# 2022-4T-MNT-3.net
KiCad netlist of a schematic drawn in EasyEDA Pro
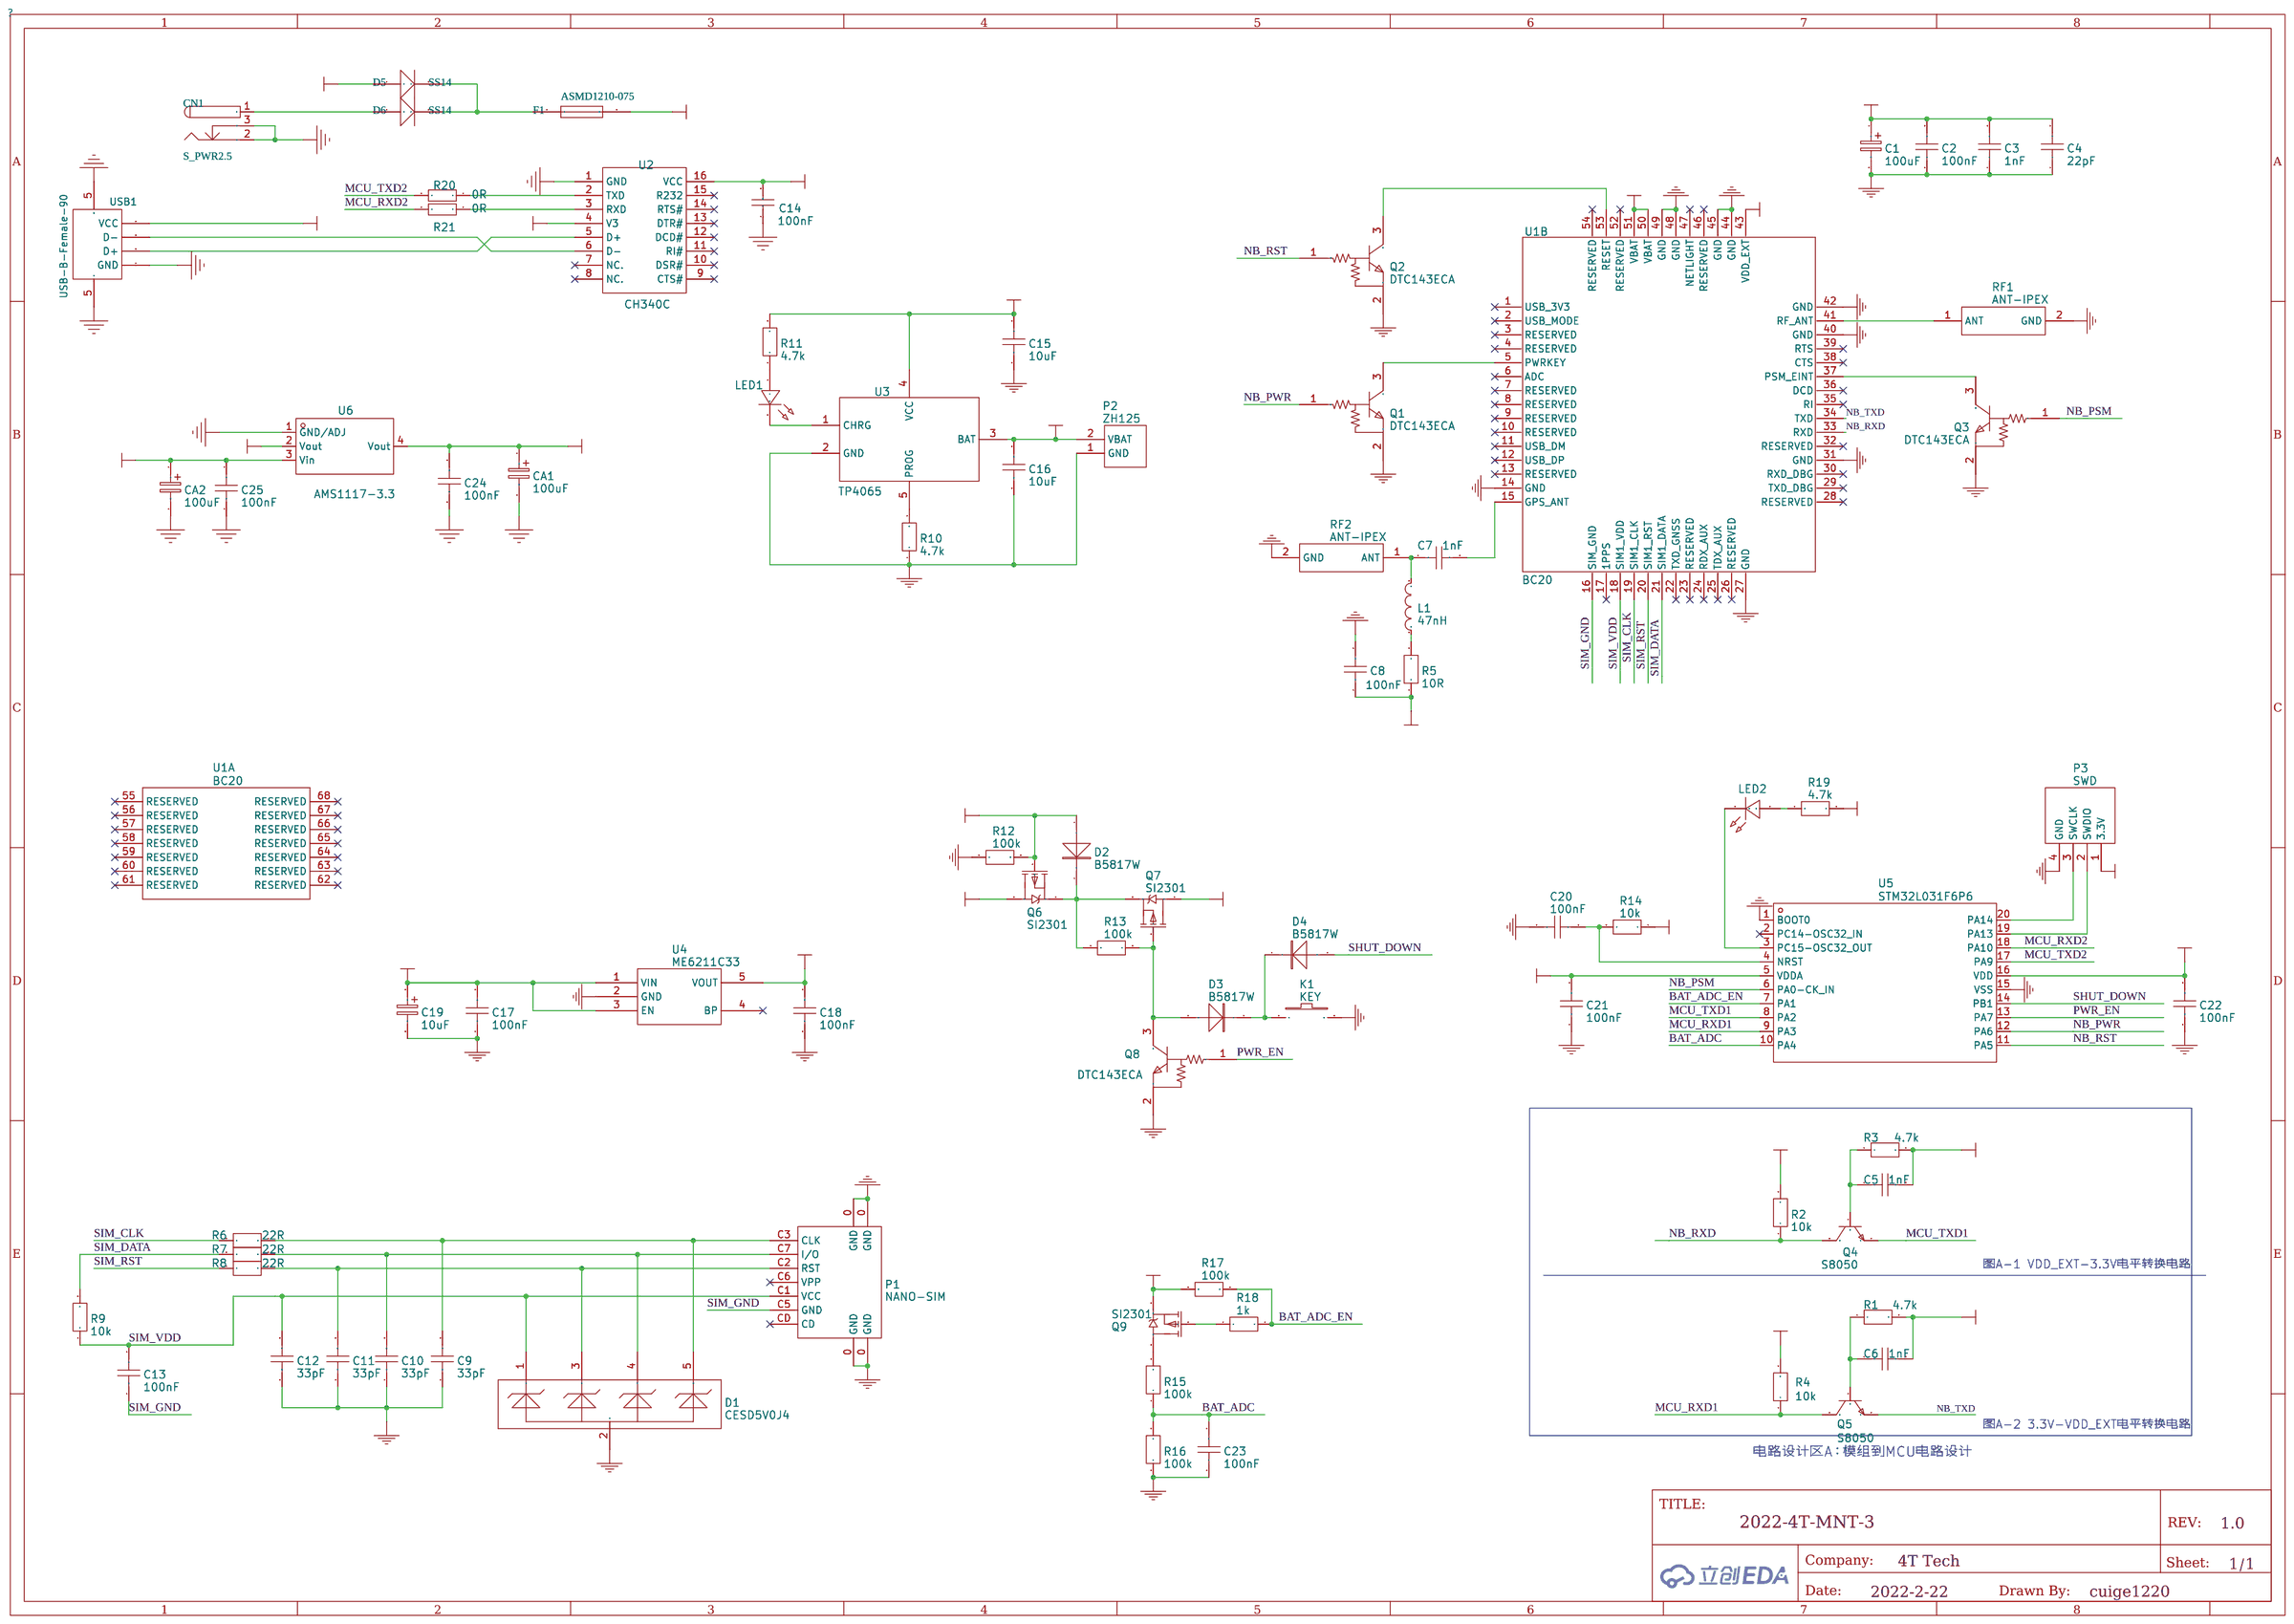
[diagram p0: schematic sheet]

(export (version "E")
  (design (tool "Eeschema 10.0.6"))
  (components
    (comp (ref "C1") (value "100uF") (libsource (lib "easyedapro") (part "100uF")))
    (comp (ref "C2")
      (value "100nF")
      (fields (field (name "Manufacturer Part") "TCC0603X7R104K500CT") (field (name "Manufacturer") "CCTC"))
      (libsource (lib "easyedapro") (part "100nF"))
    )
    (comp (ref "C3")
      (value "1nF")
      (fields (field (name "Manufacturer Part") "CL10C101JB8NNNC") (field (name "Manufacturer") "SAMSUNG"))
      (libsource (lib "easyedapro") (part "1nF"))
    )
    (comp (ref "C4") (value "22pF") (libsource (lib "easyedapro") (part "22pF")))
    (comp (ref "C5") (value "1nF") (libsource (lib "easyedapro") (part "1nF")))
    (comp (ref "C6") (value "1nF") (libsource (lib "easyedapro") (part "1nF")))
    (comp (ref "C7")
      (value "1nF")
      (fields (field (name "Manufacturer Part") "CL10C101JB8NNNC") (field (name "Manufacturer") "SAMSUNG"))
      (libsource (lib "easyedapro") (part "1nF"))
    )
    (comp (ref "C8")
      (value "100nF")
      (fields (field (name "Manufacturer Part") "TCC0603X7R104K500CT") (field (name "Manufacturer") "CCTC"))
      (libsource (lib "easyedapro") (part "100nF"))
    )
    (comp (ref "C9") (value "33pF") (libsource (lib "easyedapro") (part "33pF")))
    (comp (ref "C10") (value "33pF") (libsource (lib "easyedapro") (part "33pF")))
    (comp (ref "C11") (value "33pF") (libsource (lib "easyedapro") (part "33pF")))
    (comp (ref "C12") (value "33pF") (libsource (lib "easyedapro") (part "33pF")))
    (comp (ref "C13")
      (value "100nF")
      (fields (field (name "Manufacturer Part") "TCC0603X7R104K500CT") (field (name "Manufacturer") "CCTC"))
      (libsource (lib "easyedapro") (part "100nF"))
    )
    (comp (ref "C14")
      (value "100nF")
      (fields (field (name "Manufacturer Part") "0805F104M500NT") (field (name "Manufacturer") "FH"))
      (libsource (lib "") (part "100nF_1"))
    )
    (comp (ref "C15") (value "10uF") (libsource (lib "easyedapro") (part "10uF")))
    (comp (ref "C16") (value "10uF") (libsource (lib "easyedapro") (part "10uF")))
    (comp (ref "C17") (value "100nF") (libsource (lib "easyedapro") (part "100nF")))
    (comp (ref "C18") (value "100nF") (libsource (lib "easyedapro") (part "100nF")))
    (comp (ref "C19") (value "10uF") (libsource (lib "") (part "10uF_1")))
    (comp (ref "C20")
      (value "100nF")
      (fields (field (name "Manufacturer Part") "TCC0603X7R104K500CT") (field (name "Manufacturer") "CCTC"))
      (libsource (lib "easyedapro") (part "100nF"))
    )
    (comp (ref "C21")
      (value "100nF")
      (fields (field (name "Manufacturer Part") "TCC0603X7R104K500CT") (field (name "Manufacturer") "CCTC"))
      (libsource (lib "easyedapro") (part "100nF"))
    )
    (comp (ref "C22")
      (value "100nF")
      (fields (field (name "Manufacturer Part") "TCC0603X7R104K500CT") (field (name "Manufacturer") "CCTC"))
      (libsource (lib "easyedapro") (part "100nF"))
    )
    (comp (ref "C23")
      (value "100nF")
      (fields (field (name "Manufacturer Part") "TCC0603X7R104K500CT") (field (name "Manufacturer") "CCTC"))
      (libsource (lib "easyedapro") (part "100nF"))
    )
    (comp (ref "C24") (value "100nF") (libsource (lib "easyedapro") (part "100nF")))
    (comp (ref "C25") (value "100nF") (libsource (lib "easyedapro") (part "100nF")))
    (comp (ref "CA1") (value "100uF") (libsource (lib "easyedapro") (part "100uF")))
    (comp (ref "CA2") (value "100uF") (libsource (lib "easyedapro") (part "100uF")))
    (comp (ref "CN1") (value "S_PWR2.5") (libsource (lib "easyedapro") (part "S_PWR2.5")))
    (comp (ref "D1")
      (value "CESD5V0J4")
      (fields (field (name "Manufacturer") "CJ江苏长电"))
      (libsource (lib "easyedapro") (part "CESD5V0J4"))
    )
    (comp (ref "D2")
      (value "B5817W")
      (fields (field (name "Manufacturer") "CJ江苏长电"))
      (libsource (lib "easyedapro") (part "B5817W"))
    )
    (comp (ref "D3")
      (value "B5817W")
      (fields (field (name "Manufacturer") "CJ江苏长电"))
      (libsource (lib "easyedapro") (part "B5817W"))
    )
    (comp (ref "D4")
      (value "B5817W")
      (fields (field (name "Manufacturer") "CJ江苏长电"))
      (libsource (lib "easyedapro") (part "B5817W"))
    )
    (comp (ref "D5")
      (value "SS14")
      (fields (field (name "Publisher") "Altium Limited"))
      (libsource (lib "easyedapro") (part "SS14"))
    )
    (comp (ref "D6")
      (value "SS14")
      (fields (field (name "Publisher") "Altium Limited"))
      (libsource (lib "easyedapro") (part "SS14"))
    )
    (comp (ref "F1")
      (value "ASMD1210-075")
      (fields (field (name "Publisher") "Altium Limited"))
      (libsource (lib "easyedapro") (part "ASMD1210-075"))
    )
    (comp (ref "K1")
      (value "KEY")
      (fields (field (name "Manufacturer Part") "TSA365G00D-250") (field (name "Manufacturer") "BRIGHT(博瑞泰)"))
      (libsource (lib "easyedapro") (part "KEY"))
    )
    (comp (ref "L1") (value "47nH") (libsource (lib "easyedapro") (part "47nH")))
    (comp (ref "LED1")
      (value "LED-0805_R")
      (fields
        (field (name "Manufacturer Part") "17-21SURC/S530-A3/TR8")
        (field (name "Manufacturer") "EVERLIGHT(台湾亿光)")
      )
      (libsource (lib "easyedapro") (part "LED-0805_R"))
    )
    (comp (ref "LED2")
      (value "LED-0805_R")
      (fields
        (field (name "Manufacturer Part") "17-21SURC/S530-A3/TR8")
        (field (name "Manufacturer") "EVERLIGHT(台湾亿光)")
      )
      (libsource (lib "easyedapro") (part "LED-0805_R"))
    )
    (comp (ref "P1")
      (value "NANO-SIM")
      (fields (field (name "Manufacturer Part") "SMN-303") (field (name "Manufacturer") "XUNPU(讯普)"))
      (libsource (lib "easyedapro") (part "NANO-SIM"))
    )
    (comp (ref "P2")
      (value "ZH125")
      (fields (field (name "Manufacturer Part") "1251SMT-2P 卧贴") (field (name "Manufacturer") "Ckmtw(灿科盟)"))
      (libsource (lib "easyedapro") (part "ZH125"))
    )
    (comp (ref "P3")
      (value "SWD")
      (fields (field (name "Manufacturer Part") "A2541WV-4P") (field (name "Manufacturer") "CJT(长江连接器)"))
      (libsource (lib "easyedapro") (part "SWD"))
    )
    (comp (ref "Q1")
      (value "DTC143ECA")
      (fields (field (name "Manufacturer") "CJ江苏长电"))
      (libsource (lib "easyedapro") (part "DTC143ECA"))
    )
    (comp (ref "Q2")
      (value "DTC143ECA")
      (fields (field (name "Manufacturer") "CJ江苏长电"))
      (libsource (lib "easyedapro") (part "DTC143ECA"))
    )
    (comp (ref "Q3")
      (value "DTC143ECA")
      (fields (field (name "Manufacturer") "CJ江苏长电"))
      (libsource (lib "") (part "DTC143ECA_2"))
    )
    (comp (ref "Q4")
      (value "S8050")
      (fields (field (name "Manufacturer") "BORN伯恩半导体"))
      (libsource (lib "easyedapro") (part "S8050"))
    )
    (comp (ref "Q5")
      (value "S8050")
      (fields (field (name "Manufacturer") "BORN伯恩半导体"))
      (libsource (lib "easyedapro") (part "S8050"))
    )
    (comp (ref "Q6")
      (value "SI2301")
      (fields (field (name "Manufacturer") "Hottech(合科泰)"))
      (libsource (lib "easyedapro") (part "SI2301"))
    )
    (comp (ref "Q7")
      (value "SI2301")
      (fields (field (name "Manufacturer") "Hottech(合科泰)"))
      (libsource (lib "easyedapro") (part "SI2301"))
    )
    (comp (ref "Q8")
      (value "DTC143ECA")
      (fields (field (name "Manufacturer") "CJ江苏长电"))
      (libsource (lib "") (part "DTC143ECA_1"))
    )
    (comp (ref "Q9")
      (value "SI2301")
      (fields (field (name "Manufacturer") "Hottech(合科泰)"))
      (libsource (lib "") (part "SI2301_1"))
    )
    (comp (ref "R1") (value "4.7k") (libsource (lib "easyedapro") (part "4.7k")))
    (comp (ref "R2") (value "10k") (libsource (lib "easyedapro") (part "10k")))
    (comp (ref "R3") (value "4.7k") (libsource (lib "easyedapro") (part "4.7k")))
    (comp (ref "R4") (value "10k") (libsource (lib "easyedapro") (part "10k")))
    (comp (ref "R5") (value "10R") (libsource (lib "easyedapro") (part "10R")))
    (comp (ref "R6") (value "22R") (libsource (lib "easyedapro") (part "22R")))
    (comp (ref "R7") (value "22R") (libsource (lib "easyedapro") (part "22R")))
    (comp (ref "R8") (value "22R") (libsource (lib "easyedapro") (part "22R")))
    (comp (ref "R9") (value "10k") (libsource (lib "easyedapro") (part "10k")))
    (comp (ref "R10") (value "4.7k") (libsource (lib "easyedapro") (part "4.7k")))
    (comp (ref "R11") (value "4.7k") (libsource (lib "easyedapro") (part "4.7k")))
    (comp (ref "R12") (value "100k") (libsource (lib "easyedapro") (part "100k")))
    (comp (ref "R13") (value "100k") (libsource (lib "easyedapro") (part "100k")))
    (comp (ref "R14") (value "10k") (libsource (lib "easyedapro") (part "10k")))
    (comp (ref "R15") (value "100k") (libsource (lib "easyedapro") (part "100k")))
    (comp (ref "R16") (value "100k") (libsource (lib "easyedapro") (part "100k")))
    (comp (ref "R17") (value "100k") (libsource (lib "easyedapro") (part "100k")))
    (comp (ref "R18") (value "1k") (libsource (lib "easyedapro") (part "1k")))
    (comp (ref "R19") (value "4.7k") (libsource (lib "easyedapro") (part "4.7k")))
    (comp (ref "R20")
      (value "0R")
      (fields (field (name "Manufacturer Part") "080500J0104T5E") (field (name "Manufacturer") "UniOhm"))
      (libsource (lib "easyedapro") (part "0R"))
    )
    (comp (ref "R21")
      (value "0R")
      (fields (field (name "Manufacturer Part") "080500J0104T5E") (field (name "Manufacturer") "UniOhm"))
      (libsource (lib "easyedapro") (part "0R"))
    )
    (comp (ref "RF1")
      (value "ANT-IPEX")
      (fields
        (field (name "Manufacturer Part") "KH-IPEX-K501-29")
        (field (name "Manufacturer") "Shenzhen Kinghelm Elec")
      )
      (libsource (lib "easyedapro") (part "ANT-IPEX"))
    )
    (comp (ref "RF2")
      (value "ANT-IPEX")
      (fields
        (field (name "Manufacturer Part") "KH-IPEX-K501-29")
        (field (name "Manufacturer") "Shenzhen Kinghelm Elec")
      )
      (libsource (lib "easyedapro") (part "ANT-IPEX"))
    )
    (comp (ref "U1")
      (value "BC20")
      (fields (field (name "Manufacturer Part") "BC20NA-04-STD") (field (name "Manufacturer") "上海移远"))
      (libsource (lib "easyedapro") (part "BC20"))
    )
    (comp (ref "U2")
      (value "CH340C")
      (fields (field (name "Manufacturer") "WCH"))
      (libsource (lib "easyedapro") (part "CH340C"))
    )
    (comp (ref "U3")
      (value "TP4065")
      (fields
        (field (name "Manufacturer Part") "TP4065-4.2V-SOT25-R")
        (field (name "Manufacturer") "TOPPOWER(南京拓微)")
      )
      (libsource (lib "easyedapro") (part "TP4065"))
    )
    (comp (ref "U4")
      (value "ME6211C33")
      (fields
        (field (name "Manufacturer Part") "ME6211C33M5G-N")
        (field (name "Manufacturer") "MICRONE(南京微盟)")
      )
      (libsource (lib "easyedapro") (part "ME6211C33"))
    )
    (comp (ref "U5")
      (value "STM32L031F6P6")
      (fields (field (name "Manufacturer") "ST(意法半导体)"))
      (libsource (lib "easyedapro") (part "STM32L031F6P6"))
    )
    (comp (ref "U6")
      (value "AMS1117-3.3")
      (fields (field (name "Manufacturer") "AMS"))
      (libsource (lib "easyedapro") (part "AMS1117-3.3"))
    )
    (comp (ref "USB1")
      (value "USB-B-Female-90")
      (fields (field (name "Manufacturer Part") "USB-BF90") (field (name "Manufacturer") "ValuePro"))
      (libsource (lib "easyedapro") (part "USB-B-Female-90"))
    )
  )
  (nets
    (net (code "1") (name "+5V0") (class "Default")
      (node (ref "C25") (pin "2") (pinfunction "2_2") (pintype "input"))
      (node (ref "CA2") (pin "1") (pinfunction "1_1") (pintype "input"))
      (node (ref "F1") (pin "2") (pinfunction "2_2") (pintype "input"))
      (node (ref "U6") (pin "3") (pinfunction "Vin_3") (pintype "input"))
    )
    (net (code "2") (name "/BAT_ADC") (class "Default")
      (node (ref "C23") (pin "2") (pinfunction "2_2") (pintype "input"))
      (node (ref "R15") (pin "1") (pinfunction "1_1") (pintype "input"))
      (node (ref "R16") (pin "2") (pinfunction "2_2") (pintype "input"))
      (node (ref "U5") (pin "10") (pinfunction "PA4_10") (pintype "input"))
    )
    (net (code "3") (name "/BAT_ADC_EN") (class "Default")
      (node (ref "R17") (pin "2") (pinfunction "2_2") (pintype "input"))
      (node (ref "R18") (pin "2") (pinfunction "2_2") (pintype "input"))
      (node (ref "U5") (pin "7") (pinfunction "PA1_7") (pintype "input"))
    )
    (net (code "4") (name "/MCU_RXD1") (class "Default")
      (node (ref "Q5") (pin "3") (pinfunction "C_3") (pintype "input"))
      (node (ref "R4") (pin "1") (pinfunction "1_1") (pintype "input"))
      (node (ref "U5") (pin "9") (pinfunction "PA3_9") (pintype "input"))
    )
    (net (code "5") (name "/MCU_RXD2") (class "Default")
      (node (ref "R21") (pin "2") (pinfunction "2_2") (pintype "input"))
      (node (ref "U5") (pin "18") (pinfunction "PA10_18") (pintype "input"))
    )
    (net (code "6") (name "/MCU_TXD1") (class "Default")
      (node (ref "Q4") (pin "2") (pinfunction "E_2") (pintype "input"))
      (node (ref "U5") (pin "8") (pinfunction "PA2_8") (pintype "input"))
    )
    (net (code "7") (name "/MCU_TXD2") (class "Default")
      (node (ref "R20") (pin "2") (pinfunction "2_2") (pintype "input"))
      (node (ref "U5") (pin "17") (pinfunction "PA9_17") (pintype "input"))
    )
    (net (code "8") (name "/NB_PSM") (class "Default")
      (node (ref "Q3") (pin "1") (pinfunction "B_1") (pintype "input"))
      (node (ref "U5") (pin "6") (pinfunction "PA0-CK_IN_6") (pintype "input"))
    )
    (net (code "9") (name "/NB_PWR") (class "Default")
      (node (ref "Q1") (pin "1") (pinfunction "B_1") (pintype "input"))
      (node (ref "U5") (pin "12") (pinfunction "PA6_12") (pintype "input"))
    )
    (net (code "10") (name "/NB_RST") (class "Default")
      (node (ref "Q2") (pin "1") (pinfunction "B_1") (pintype "input"))
      (node (ref "U5") (pin "11") (pinfunction "PA5_11") (pintype "input"))
    )
    (net (code "11") (name "/NB_RXD") (class "Default")
      (node (ref "Q4") (pin "3") (pinfunction "C_3") (pintype "input"))
      (node (ref "R2") (pin "1") (pinfunction "1_1") (pintype "input"))
      (node (ref "U1") (pin "33") (pinfunction "RXD_33") (pintype "input"))
    )
    (net (code "12") (name "/NB_TXD") (class "Default")
      (node (ref "Q5") (pin "2") (pinfunction "E_2") (pintype "input"))
      (node (ref "U1") (pin "34") (pinfunction "TXD_34") (pintype "input"))
    )
    (net (code "13") (name "/PWR_EN") (class "Default")
      (node (ref "Q8") (pin "1") (pinfunction "B_1") (pintype "input"))
      (node (ref "U5") (pin "13") (pinfunction "PA7_13") (pintype "input"))
    )
    (net (code "14") (name "/SHUT_DOWN") (class "Default")
      (node (ref "D4") (pin "A") (pinfunction "A_A") (pintype "input"))
      (node (ref "U5") (pin "14") (pinfunction "PB1_14") (pintype "input"))
    )
    (net (code "15") (name "/SIM_CLK") (class "Default")
      (node (ref "R6") (pin "1") (pinfunction "1_1") (pintype "input"))
      (node (ref "U1") (pin "19") (pinfunction "SIM1_CLK_19") (pintype "input"))
    )
    (net (code "16") (name "/SIM_DATA") (class "Default")
      (node (ref "R7") (pin "1") (pinfunction "1_1") (pintype "input"))
      (node (ref "R9") (pin "2") (pinfunction "2_2") (pintype "input"))
      (node (ref "U1") (pin "21") (pinfunction "SIM1_DATA_21") (pintype "input"))
    )
    (net (code "17") (name "/SIM_GND") (class "Default")
      (node (ref "C13") (pin "1") (pinfunction "1_1") (pintype "input"))
      (node (ref "P1") (pin "C5") (pinfunction "GND_C5") (pintype "input"))
      (node (ref "U1") (pin "16") (pinfunction "SIM_GND_16") (pintype "input"))
    )
    (net (code "18") (name "/SIM_RST") (class "Default")
      (node (ref "R8") (pin "1") (pinfunction "1_1") (pintype "input"))
      (node (ref "U1") (pin "20") (pinfunction "SIM1_RST_20") (pintype "input"))
    )
    (net (code "19") (name "/SIM_VDD") (class "Default")
      (node (ref "C12") (pin "2") (pinfunction "2_2") (pintype "input"))
      (node (ref "C13") (pin "2") (pinfunction "2_2") (pintype "input"))
      (node (ref "D1") (pin "1") (pinfunction "1_1") (pintype "input"))
      (node (ref "P1") (pin "C1") (pinfunction "VCC_C1") (pintype "input"))
      (node (ref "R9") (pin "1") (pinfunction "1_1") (pintype "input"))
      (node (ref "U1") (pin "18") (pinfunction "SIM1_VDD_18") (pintype "input"))
    )
    (net (code "20") (name "3.3V") (class "Default")
      (node (ref "C1") (pin "1") (pinfunction "1_1") (pintype "input"))
      (node (ref "C14") (pin "2") (pinfunction "2_2") (pintype "input"))
      (node (ref "C18") (pin "2") (pinfunction "2_2") (pintype "input"))
      (node (ref "C2") (pin "2") (pinfunction "2_2") (pintype "input"))
      (node (ref "C21") (pin "2") (pinfunction "2_2") (pintype "input"))
      (node (ref "C22") (pin "2") (pinfunction "2_2") (pintype "input"))
      (node (ref "C24") (pin "2") (pinfunction "2_2") (pintype "input"))
      (node (ref "C3") (pin "2") (pinfunction "2_2") (pintype "input"))
      (node (ref "C4") (pin "2") (pinfunction "2_2") (pintype "input"))
      (node (ref "C5") (pin "2") (pinfunction "2_2") (pintype "input"))
      (node (ref "C8") (pin "1") (pinfunction "1_1") (pintype "input"))
      (node (ref "CA1") (pin "1") (pinfunction "1_1") (pintype "input"))
      (node (ref "P3") (pin "1") (pinfunction "3.3V_1") (pintype "input"))
      (node (ref "R14") (pin "1") (pinfunction "1_1") (pintype "input"))
      (node (ref "R19") (pin "2") (pinfunction "2_2") (pintype "input"))
      (node (ref "R3") (pin "2") (pinfunction "2_2") (pintype "input"))
      (node (ref "R4") (pin "2") (pinfunction "2_2") (pintype "input"))
      (node (ref "R5") (pin "1") (pinfunction "1_1") (pintype "input"))
      (node (ref "U1") (pin "50") (pinfunction "VBAT_50") (pintype "input"))
      (node (ref "U1") (pin "51") (pinfunction "VBAT_51") (pintype "input"))
      (node (ref "U2") (pin "16") (pinfunction "VCC_16") (pintype "input"))
      (node (ref "U2") (pin "4") (pinfunction "V3_4") (pintype "input"))
      (node (ref "U4") (pin "5") (pinfunction "VOUT_5") (pintype "input"))
      (node (ref "U5") (pin "16") (pinfunction "VDD_16") (pintype "input"))
      (node (ref "U5") (pin "5") (pinfunction "VDDA_5") (pintype "input"))
      (node (ref "U6") (pin "2") (pinfunction "Vout_2") (pintype "input"))
      (node (ref "U6") (pin "4") (pinfunction "Vout_4") (pintype "input"))
    )
    (net (code "21") (name "GND") (class "Default")
      (node (ref "C1") (pin "2") (pinfunction "2_2") (pintype "input"))
      (node (ref "C10") (pin "1") (pinfunction "1_1") (pintype "input"))
      (node (ref "C11") (pin "1") (pinfunction "1_1") (pintype "input"))
      (node (ref "C12") (pin "1") (pinfunction "1_1") (pintype "input"))
      (node (ref "C14") (pin "1") (pinfunction "1_1") (pintype "input"))
      (node (ref "C15") (pin "1") (pinfunction "1_1") (pintype "input"))
      (node (ref "C16") (pin "1") (pinfunction "1_1") (pintype "input"))
      (node (ref "C17") (pin "1") (pinfunction "1_1") (pintype "input"))
      (node (ref "C18") (pin "1") (pinfunction "1_1") (pintype "input"))
      (node (ref "C19") (pin "2") (pinfunction "2_2") (pintype "input"))
      (node (ref "C2") (pin "1") (pinfunction "1_1") (pintype "input"))
      (node (ref "C20") (pin "1") (pinfunction "1_1") (pintype "input"))
      (node (ref "C21") (pin "1") (pinfunction "1_1") (pintype "input"))
      (node (ref "C22") (pin "1") (pinfunction "1_1") (pintype "input"))
      (node (ref "C23") (pin "1") (pinfunction "1_1") (pintype "input"))
      (node (ref "C24") (pin "1") (pinfunction "1_1") (pintype "input"))
      (node (ref "C25") (pin "1") (pinfunction "1_1") (pintype "input"))
      (node (ref "C3") (pin "1") (pinfunction "1_1") (pintype "input"))
      (node (ref "C4") (pin "1") (pinfunction "1_1") (pintype "input"))
      (node (ref "C8") (pin "2") (pinfunction "2_2") (pintype "input"))
      (node (ref "C9") (pin "1") (pinfunction "1_1") (pintype "input"))
      (node (ref "CA1") (pin "2") (pinfunction "2_2") (pintype "input"))
      (node (ref "CA2") (pin "2") (pinfunction "2_2") (pintype "input"))
      (node (ref "CN1") (pin "2") (pinfunction "2_2") (pintype "input"))
      (node (ref "CN1") (pin "3") (pinfunction "3_3") (pintype "input"))
      (node (ref "D1") (pin "2") (pinfunction "2_2") (pintype "input"))
      (node (ref "K1") (pin "2") (pinfunction "2_2") (pintype "input"))
      (node (ref "P1") (pin "0") (pinfunction "GND_0") (pintype "input"))
      (node (ref "P2") (pin "1") (pinfunction "GND_1") (pintype "input"))
      (node (ref "P3") (pin "4") (pinfunction "GND_4") (pintype "input"))
      (node (ref "Q1") (pin "2") (pinfunction "E_2") (pintype "input"))
      (node (ref "Q2") (pin "2") (pinfunction "E_2") (pintype "input"))
      (node (ref "Q3") (pin "2") (pinfunction "E_2") (pintype "input"))
      (node (ref "Q8") (pin "2") (pinfunction "E_2") (pintype "input"))
      (node (ref "R10") (pin "1") (pinfunction "1_1") (pintype "input"))
      (node (ref "R12") (pin "1") (pinfunction "1_1") (pintype "input"))
      (node (ref "R16") (pin "1") (pinfunction "1_1") (pintype "input"))
      (node (ref "RF1") (pin "2") (pinfunction "GND_2") (pintype "input"))
      (node (ref "RF2") (pin "2") (pinfunction "GND_2") (pintype "input"))
      (node (ref "U1") (pin "14") (pinfunction "GND_14") (pintype "input"))
      (node (ref "U1") (pin "27") (pinfunction "GND_27") (pintype "input"))
      (node (ref "U1") (pin "31") (pinfunction "GND_31") (pintype "input"))
      (node (ref "U1") (pin "40") (pinfunction "GND_40") (pintype "input"))
      (node (ref "U1") (pin "42") (pinfunction "GND_42") (pintype "input"))
      (node (ref "U1") (pin "44") (pinfunction "GND_44") (pintype "input"))
      (node (ref "U1") (pin "45") (pinfunction "GND_45") (pintype "input"))
      (node (ref "U1") (pin "48") (pinfunction "GND_48") (pintype "input"))
      (node (ref "U1") (pin "49") (pinfunction "GND_49") (pintype "input"))
      (node (ref "U2") (pin "1") (pinfunction "GND_1") (pintype "input"))
      (node (ref "U3") (pin "2") (pinfunction "GND_2") (pintype "input"))
      (node (ref "U4") (pin "2") (pinfunction "GND_2") (pintype "input"))
      (node (ref "U5") (pin "1") (pinfunction "BOOT0_1") (pintype "input"))
      (node (ref "U5") (pin "15") (pinfunction "VSS_15") (pintype "input"))
      (node (ref "U6") (pin "1") (pinfunction "GND/ADJ_1") (pintype "input"))
      (node (ref "USB1") (pin "4") (pinfunction "GND_4") (pintype "input"))
      (node (ref "USB1") (pin "5") (pinfunction "SH1_5") (pintype "input"))
    )
    (net (code "22") (name "Net-(D3-PadK)") (class "Default")
      (node (ref "D3") (pin "K") (pinfunction "K_K") (pintype "input"))
      (node (ref "D4") (pin "K") (pinfunction "K_K") (pintype "input"))
      (node (ref "K1") (pin "1") (pinfunction "1_1") (pintype "input"))
    )
    (net (code "23") (name "Net-(D5-K)") (class "Default")
      (node (ref "D5") (pin "2") (pinfunction "K_2") (pintype "input"))
      (node (ref "D6") (pin "2") (pinfunction "K_2") (pintype "input"))
      (node (ref "F1") (pin "1") (pinfunction "1_1") (pintype "input"))
    )
    (net (code "24") (name "Net-(D6-A)") (class "Default")
      (node (ref "CN1") (pin "1") (pinfunction "1_1") (pintype "input"))
      (node (ref "D6") (pin "1") (pinfunction "A_1") (pintype "input"))
    )
    (net (code "25") (name "Net-(L1-Pad1)") (class "Default")
      (node (ref "L1") (pin "1") (pinfunction "1_1") (pintype "input"))
      (node (ref "R5") (pin "2") (pinfunction "2_2") (pintype "input"))
    )
    (net (code "26") (name "Net-(LED1-Pad1)") (class "Default")
      (node (ref "LED1") (pin "1") (pinfunction "1_1") (pintype "input"))
      (node (ref "R11") (pin "1") (pinfunction "1_1") (pintype "input"))
    )
    (net (code "27") (name "Net-(LED2-Pad1)") (class "Default")
      (node (ref "LED2") (pin "1") (pinfunction "1_1") (pintype "input"))
      (node (ref "R19") (pin "1") (pinfunction "1_1") (pintype "input"))
    )
    (net (code "28") (name "Net-(P1-CLK)") (class "Default")
      (node (ref "C9") (pin "2") (pinfunction "2_2") (pintype "input"))
      (node (ref "D1") (pin "5") (pinfunction "5_5") (pintype "input"))
      (node (ref "P1") (pin "C3") (pinfunction "CLK_C3") (pintype "input"))
      (node (ref "R6") (pin "2") (pinfunction "2_2") (pintype "input"))
    )
    (net (code "29") (name "Net-(P1-I{slash}O)") (class "Default")
      (node (ref "C10") (pin "2") (pinfunction "2_2") (pintype "input"))
      (node (ref "D1") (pin "4") (pinfunction "4_4") (pintype "input"))
      (node (ref "P1") (pin "C7") (pinfunction "I/O_C7") (pintype "input"))
      (node (ref "R7") (pin "2") (pinfunction "2_2") (pintype "input"))
    )
    (net (code "30") (name "Net-(P1-RST)") (class "Default")
      (node (ref "C11") (pin "2") (pinfunction "2_2") (pintype "input"))
      (node (ref "D1") (pin "3") (pinfunction "3_3") (pintype "input"))
      (node (ref "P1") (pin "C2") (pinfunction "RST_C2") (pintype "input"))
      (node (ref "R8") (pin "2") (pinfunction "2_2") (pintype "input"))
    )
    (net (code "31") (name "Net-(P3-SWCLK)") (class "Default")
      (node (ref "P3") (pin "3") (pinfunction "SWCLK_3") (pintype "input"))
      (node (ref "U5") (pin "20") (pinfunction "PA14_20") (pintype "input"))
    )
    (net (code "32") (name "Net-(P3-SWDIO)") (class "Default")
      (node (ref "P3") (pin "2") (pinfunction "SWDIO_2") (pintype "input"))
      (node (ref "U5") (pin "19") (pinfunction "PA13_19") (pintype "input"))
    )
    (net (code "33") (name "Net-(Q1-C)") (class "Default")
      (node (ref "Q1") (pin "3") (pinfunction "C_3") (pintype "input"))
      (node (ref "U1") (pin "5") (pinfunction "PWRKEY_5") (pintype "input"))
    )
    (net (code "34") (name "Net-(Q2-C)") (class "Default")
      (node (ref "Q2") (pin "3") (pinfunction "C_3") (pintype "input"))
      (node (ref "U1") (pin "53") (pinfunction "RESET_53") (pintype "input"))
    )
    (net (code "35") (name "Net-(Q3-C)") (class "Default")
      (node (ref "Q3") (pin "3") (pinfunction "C_3") (pintype "input"))
      (node (ref "U1") (pin "37") (pinfunction "PSM_EINT_37") (pintype "input"))
    )
    (net (code "36") (name "Net-(Q4-B)") (class "Default")
      (node (ref "C5") (pin "1") (pinfunction "1_1") (pintype "input"))
      (node (ref "Q4") (pin "1") (pinfunction "B_1") (pintype "input"))
      (node (ref "R3") (pin "1") (pinfunction "1_1") (pintype "input"))
    )
    (net (code "37") (name "Net-(Q5-B)") (class "Default")
      (node (ref "C6") (pin "1") (pinfunction "1_1") (pintype "input"))
      (node (ref "Q5") (pin "1") (pinfunction "B_1") (pintype "input"))
      (node (ref "R1") (pin "1") (pinfunction "1_1") (pintype "input"))
    )
    (net (code "38") (name "Net-(Q6-S)") (class "Default")
      (node (ref "D2") (pin "K") (pinfunction "K_K") (pintype "input"))
      (node (ref "Q6") (pin "2") (pinfunction "S_2") (pintype "input"))
      (node (ref "Q7") (pin "2") (pinfunction "S_2") (pintype "input"))
      (node (ref "R13") (pin "1") (pinfunction "1_1") (pintype "input"))
    )
    (net (code "39") (name "Net-(Q7-G)") (class "Default")
      (node (ref "D3") (pin "A") (pinfunction "A_A") (pintype "input"))
      (node (ref "Q7") (pin "1") (pinfunction "G_1") (pintype "input"))
      (node (ref "Q8") (pin "3") (pinfunction "C_3") (pintype "input"))
      (node (ref "R13") (pin "2") (pinfunction "2_2") (pintype "input"))
    )
    (net (code "40") (name "Net-(Q9-D)") (class "Default")
      (node (ref "Q9") (pin "3") (pinfunction "D_3") (pintype "input"))
      (node (ref "R15") (pin "2") (pinfunction "2_2") (pintype "input"))
    )
    (net (code "41") (name "Net-(Q9-G)") (class "Default")
      (node (ref "Q9") (pin "1") (pinfunction "G_1") (pintype "input"))
      (node (ref "R18") (pin "1") (pinfunction "1_1") (pintype "input"))
    )
    (net (code "42") (name "Net-(RF1-ANT)") (class "Default")
      (node (ref "RF1") (pin "1") (pinfunction "ANT_1") (pintype "input"))
      (node (ref "U1") (pin "41") (pinfunction "RF_ANT_41") (pintype "input"))
    )
    (net (code "43") (name "Net-(RF2-ANT)") (class "Default")
      (node (ref "C7") (pin "1") (pinfunction "1_1") (pintype "input"))
      (node (ref "L1") (pin "2") (pinfunction "2_2") (pintype "input"))
      (node (ref "RF2") (pin "1") (pinfunction "ANT_1") (pintype "input"))
    )
    (net (code "44") (name "Net-(U1B-GPS_ANT)") (class "Default")
      (node (ref "C7") (pin "2") (pinfunction "2_2") (pintype "input"))
      (node (ref "U1") (pin "15") (pinfunction "GPS_ANT_15") (pintype "input"))
    )
    (net (code "45") (name "Net-(U2-D+)") (class "Default")
      (node (ref "U2") (pin "5") (pinfunction "D+_5") (pintype "input"))
      (node (ref "USB1") (pin "3") (pinfunction "D+_3") (pintype "input"))
    )
    (net (code "46") (name "Net-(U2-D-)") (class "Default")
      (node (ref "U2") (pin "6") (pinfunction "D-_6") (pintype "input"))
      (node (ref "USB1") (pin "2") (pinfunction "D-_2") (pintype "input"))
    )
    (net (code "47") (name "Net-(U2-RXD)") (class "Default")
      (node (ref "R21") (pin "1") (pinfunction "1_1") (pintype "input"))
      (node (ref "U2") (pin "3") (pinfunction "RXD_3") (pintype "input"))
    )
    (net (code "48") (name "Net-(U2-TXD)") (class "Default")
      (node (ref "R20") (pin "1") (pinfunction "1_1") (pintype "input"))
      (node (ref "U2") (pin "2") (pinfunction "TXD_2") (pintype "input"))
    )
    (net (code "49") (name "Net-(U3-CHRG)") (class "Default")
      (node (ref "LED1") (pin "2") (pinfunction "2_2") (pintype "input"))
      (node (ref "U3") (pin "1") (pinfunction "CHRG_1") (pintype "input"))
    )
    (net (code "50") (name "Net-(U3-PROG)") (class "Default")
      (node (ref "R10") (pin "2") (pinfunction "2_2") (pintype "input"))
      (node (ref "U3") (pin "5") (pinfunction "PROG_5") (pintype "input"))
    )
    (net (code "51") (name "Net-(U5-NRST)") (class "Default")
      (node (ref "C20") (pin "2") (pinfunction "2_2") (pintype "input"))
      (node (ref "R14") (pin "2") (pinfunction "2_2") (pintype "input"))
      (node (ref "U5") (pin "4") (pinfunction "NRST_4") (pintype "input"))
    )
    (net (code "52") (name "Net-(U5-PC15-OSC32_OUT)") (class "Default")
      (node (ref "LED2") (pin "2") (pinfunction "2_2") (pintype "input"))
      (node (ref "U5") (pin "3") (pinfunction "PC15-OSC32_OUT_3") (pintype "input"))
    )
    (net (code "53") (name "VBAT") (class "Default")
      (node (ref "C16") (pin "2") (pinfunction "2_2") (pintype "input"))
      (node (ref "P2") (pin "2") (pinfunction "VBAT_2") (pintype "input"))
      (node (ref "Q6") (pin "3") (pinfunction "D_3") (pintype "input"))
      (node (ref "Q9") (pin "2") (pinfunction "S_2") (pintype "input"))
      (node (ref "R17") (pin "1") (pinfunction "1_1") (pintype "input"))
      (node (ref "U3") (pin "3") (pinfunction "BAT_3") (pintype "input"))
    )
    (net (code "54") (name "VCC") (class "Default")
      (node (ref "C17") (pin "2") (pinfunction "2_2") (pintype "input"))
      (node (ref "C19") (pin "1") (pinfunction "1_1") (pintype "input"))
      (node (ref "Q7") (pin "3") (pinfunction "D_3") (pintype "input"))
      (node (ref "U4") (pin "1") (pinfunction "VIN_1") (pintype "input"))
      (node (ref "U4") (pin "3") (pinfunction "EN_3") (pintype "input"))
    )
    (net (code "55") (name "VDD_EXT") (class "Default")
      (node (ref "C6") (pin "2") (pinfunction "2_2") (pintype "input"))
      (node (ref "R1") (pin "2") (pinfunction "2_2") (pintype "input"))
      (node (ref "R2") (pin "2") (pinfunction "2_2") (pintype "input"))
      (node (ref "U1") (pin "43") (pinfunction "VDD_EXT_43") (pintype "input"))
    )
    (net (code "56") (name "VUSB") (class "Default")
      (node (ref "C15") (pin "2") (pinfunction "2_2") (pintype "input"))
      (node (ref "D2") (pin "A") (pinfunction "A_A") (pintype "input"))
      (node (ref "D5") (pin "1") (pinfunction "A_1") (pintype "input"))
      (node (ref "Q6") (pin "1") (pinfunction "G_1") (pintype "input"))
      (node (ref "R11") (pin "2") (pinfunction "2_2") (pintype "input"))
      (node (ref "R12") (pin "2") (pinfunction "2_2") (pintype "input"))
      (node (ref "U3") (pin "4") (pinfunction "VCC_4") (pintype "input"))
      (node (ref "USB1") (pin "1") (pinfunction "VCC_1") (pintype "input"))
    )
    (net (code "57") (name "unconnected-(P1-PadCD)") (class "Default")
      (node (ref "P1") (pin "CD") (pinfunction "CD_CD") (pintype "input+no_connect"))
    )
    (net (code "58") (name "unconnected-(P1-VPP-PadC6)") (class "Default")
      (node (ref "P1") (pin "C6") (pinfunction "VPP_C6") (pintype "input+no_connect"))
    )
    (net (code "59") (name "unconnected-(U1A-RESERVED-Pad55)") (class "Default")
      (node (ref "U1") (pin "55") (pinfunction "RESERVED_55") (pintype "input+no_connect"))
    )
    (net (code "60") (name "unconnected-(U1A-RESERVED-Pad56)") (class "Default")
      (node (ref "U1") (pin "56") (pinfunction "RESERVED_56") (pintype "input+no_connect"))
    )
    (net (code "61") (name "unconnected-(U1A-RESERVED-Pad57)") (class "Default")
      (node (ref "U1") (pin "57") (pinfunction "RESERVED_57") (pintype "input+no_connect"))
    )
    (net (code "62") (name "unconnected-(U1A-RESERVED-Pad58)") (class "Default")
      (node (ref "U1") (pin "58") (pinfunction "RESERVED_58") (pintype "input+no_connect"))
    )
    (net (code "63") (name "unconnected-(U1A-RESERVED-Pad59)") (class "Default")
      (node (ref "U1") (pin "59") (pinfunction "RESERVED_59") (pintype "input+no_connect"))
    )
    (net (code "64") (name "unconnected-(U1A-RESERVED-Pad60)") (class "Default")
      (node (ref "U1") (pin "60") (pinfunction "RESERVED_60") (pintype "input+no_connect"))
    )
    (net (code "65") (name "unconnected-(U1A-RESERVED-Pad61)") (class "Default")
      (node (ref "U1") (pin "61") (pinfunction "RESERVED_61") (pintype "input+no_connect"))
    )
    (net (code "66") (name "unconnected-(U1A-RESERVED-Pad62)") (class "Default")
      (node (ref "U1") (pin "62") (pinfunction "RESERVED_62") (pintype "input+no_connect"))
    )
    (net (code "67") (name "unconnected-(U1A-RESERVED-Pad63)") (class "Default")
      (node (ref "U1") (pin "63") (pinfunction "RESERVED_63") (pintype "input+no_connect"))
    )
    (net (code "68") (name "unconnected-(U1A-RESERVED-Pad64)") (class "Default")
      (node (ref "U1") (pin "64") (pinfunction "RESERVED_64") (pintype "input+no_connect"))
    )
    (net (code "69") (name "unconnected-(U1A-RESERVED-Pad65)") (class "Default")
      (node (ref "U1") (pin "65") (pinfunction "RESERVED_65") (pintype "input+no_connect"))
    )
    (net (code "70") (name "unconnected-(U1A-RESERVED-Pad66)") (class "Default")
      (node (ref "U1") (pin "66") (pinfunction "RESERVED_66") (pintype "input+no_connect"))
    )
    (net (code "71") (name "unconnected-(U1A-RESERVED-Pad67)") (class "Default")
      (node (ref "U1") (pin "67") (pinfunction "RESERVED_67") (pintype "input+no_connect"))
    )
    (net (code "72") (name "unconnected-(U1A-RESERVED-Pad68)") (class "Default")
      (node (ref "U1") (pin "68") (pinfunction "RESERVED_68") (pintype "input+no_connect"))
    )
    (net (code "73") (name "unconnected-(U1B-1PPS-Pad17)") (class "Default")
      (node (ref "U1") (pin "17") (pinfunction "1PPS_17") (pintype "input+no_connect"))
    )
    (net (code "74") (name "unconnected-(U1B-ADC-Pad6)") (class "Default")
      (node (ref "U1") (pin "6") (pinfunction "ADC_6") (pintype "input+no_connect"))
    )
    (net (code "75") (name "unconnected-(U1B-CTS-Pad38)") (class "Default")
      (node (ref "U1") (pin "38") (pinfunction "CTS_38") (pintype "input+no_connect"))
    )
    (net (code "76") (name "unconnected-(U1B-DCD-Pad36)") (class "Default")
      (node (ref "U1") (pin "36") (pinfunction "DCD_36") (pintype "input+no_connect"))
    )
    (net (code "77") (name "unconnected-(U1B-NETLIGHT-Pad47)") (class "Default")
      (node (ref "U1") (pin "47") (pinfunction "NETLIGHT_47") (pintype "input+no_connect"))
    )
    (net (code "78") (name "unconnected-(U1B-RDX_AUX-Pad24)") (class "Default")
      (node (ref "U1") (pin "24") (pinfunction "RDX_AUX_24") (pintype "input+no_connect"))
    )
    (net (code "79") (name "unconnected-(U1B-RESERVED-Pad3)") (class "Default")
      (node (ref "U1") (pin "3") (pinfunction "RESERVED_3") (pintype "input+no_connect"))
    )
    (net (code "80") (name "unconnected-(U1B-RESERVED-Pad4)") (class "Default")
      (node (ref "U1") (pin "4") (pinfunction "RESERVED_4") (pintype "input+no_connect"))
    )
    (net (code "81") (name "unconnected-(U1B-RESERVED-Pad7)") (class "Default")
      (node (ref "U1") (pin "7") (pinfunction "RESERVED_7") (pintype "input+no_connect"))
    )
    (net (code "82") (name "unconnected-(U1B-RESERVED-Pad8)") (class "Default")
      (node (ref "U1") (pin "8") (pinfunction "RESERVED_8") (pintype "input+no_connect"))
    )
    (net (code "83") (name "unconnected-(U1B-RESERVED-Pad9)") (class "Default")
      (node (ref "U1") (pin "9") (pinfunction "RESERVED_9") (pintype "input+no_connect"))
    )
    (net (code "84") (name "unconnected-(U1B-RESERVED-Pad10)") (class "Default")
      (node (ref "U1") (pin "10") (pinfunction "RESERVED_10") (pintype "input+no_connect"))
    )
    (net (code "85") (name "unconnected-(U1B-RESERVED-Pad13)") (class "Default")
      (node (ref "U1") (pin "13") (pinfunction "RESERVED_13") (pintype "input+no_connect"))
    )
    (net (code "86") (name "unconnected-(U1B-RESERVED-Pad23)") (class "Default")
      (node (ref "U1") (pin "23") (pinfunction "RESERVED_23") (pintype "input+no_connect"))
    )
    (net (code "87") (name "unconnected-(U1B-RESERVED-Pad26)") (class "Default")
      (node (ref "U1") (pin "26") (pinfunction "RESERVED_26") (pintype "input+no_connect"))
    )
    (net (code "88") (name "unconnected-(U1B-RESERVED-Pad28)") (class "Default")
      (node (ref "U1") (pin "28") (pinfunction "RESERVED_28") (pintype "input+no_connect"))
    )
    (net (code "89") (name "unconnected-(U1B-RESERVED-Pad32)") (class "Default")
      (node (ref "U1") (pin "32") (pinfunction "RESERVED_32") (pintype "input+no_connect"))
    )
    (net (code "90") (name "unconnected-(U1B-RESERVED-Pad46)") (class "Default")
      (node (ref "U1") (pin "46") (pinfunction "RESERVED_46") (pintype "input+no_connect"))
    )
    (net (code "91") (name "unconnected-(U1B-RESERVED-Pad52)") (class "Default")
      (node (ref "U1") (pin "52") (pinfunction "RESERVED_52") (pintype "input+no_connect"))
    )
    (net (code "92") (name "unconnected-(U1B-RESERVED-Pad54)") (class "Default")
      (node (ref "U1") (pin "54") (pinfunction "RESERVED_54") (pintype "input+no_connect"))
    )
    (net (code "93") (name "unconnected-(U1B-RI-Pad35)") (class "Default")
      (node (ref "U1") (pin "35") (pinfunction "RI_35") (pintype "input+no_connect"))
    )
    (net (code "94") (name "unconnected-(U1B-RTS-Pad39)") (class "Default")
      (node (ref "U1") (pin "39") (pinfunction "RTS_39") (pintype "input+no_connect"))
    )
    (net (code "95") (name "unconnected-(U1B-RXD_DBG-Pad30)") (class "Default")
      (node (ref "U1") (pin "30") (pinfunction "RXD_DBG_30") (pintype "input+no_connect"))
    )
    (net (code "96") (name "unconnected-(U1B-TDX_AUX-Pad25)") (class "Default")
      (node (ref "U1") (pin "25") (pinfunction "TDX_AUX_25") (pintype "input+no_connect"))
    )
    (net (code "97") (name "unconnected-(U1B-TXD_DBG-Pad29)") (class "Default")
      (node (ref "U1") (pin "29") (pinfunction "TXD_DBG_29") (pintype "input+no_connect"))
    )
    (net (code "98") (name "unconnected-(U1B-TXD_GNSS-Pad22)") (class "Default")
      (node (ref "U1") (pin "22") (pinfunction "TXD_GNSS_22") (pintype "input+no_connect"))
    )
    (net (code "99") (name "unconnected-(U1B-USB_3V3-Pad1)") (class "Default")
      (node (ref "U1") (pin "1") (pinfunction "USB_3V3_1") (pintype "input+no_connect"))
    )
    (net (code "100") (name "unconnected-(U1B-USB_DM-Pad11)") (class "Default")
      (node (ref "U1") (pin "11") (pinfunction "USB_DM_11") (pintype "input+no_connect"))
    )
    (net (code "101") (name "unconnected-(U1B-USB_DP-Pad12)") (class "Default")
      (node (ref "U1") (pin "12") (pinfunction "USB_DP_12") (pintype "input+no_connect"))
    )
    (net (code "102") (name "unconnected-(U1B-USB_MODE-Pad2)") (class "Default")
      (node (ref "U1") (pin "2") (pinfunction "USB_MODE_2") (pintype "input+no_connect"))
    )
    (net (code "103") (name "unconnected-(U2-CTS#-Pad9)") (class "Default")
      (node (ref "U2") (pin "9") (pinfunction "CTS#_9") (pintype "input+no_connect"))
    )
    (net (code "104") (name "unconnected-(U2-DCD#-Pad12)") (class "Default")
      (node (ref "U2") (pin "12") (pinfunction "DCD#_12") (pintype "input+no_connect"))
    )
    (net (code "105") (name "unconnected-(U2-DSR#-Pad10)") (class "Default")
      (node (ref "U2") (pin "10") (pinfunction "DSR#_10") (pintype "input+no_connect"))
    )
    (net (code "106") (name "unconnected-(U2-DTR#-Pad13)") (class "Default")
      (node (ref "U2") (pin "13") (pinfunction "DTR#_13") (pintype "input+no_connect"))
    )
    (net (code "107") (name "unconnected-(U2-NC.-Pad7)") (class "Default")
      (node (ref "U2") (pin "7") (pinfunction "NC._7") (pintype "input+no_connect"))
    )
    (net (code "108") (name "unconnected-(U2-NC.-Pad8)") (class "Default")
      (node (ref "U2") (pin "8") (pinfunction "NC._8") (pintype "input+no_connect"))
    )
    (net (code "109") (name "unconnected-(U2-R232-Pad15)") (class "Default")
      (node (ref "U2") (pin "15") (pinfunction "R232_15") (pintype "input+no_connect"))
    )
    (net (code "110") (name "unconnected-(U2-RI#-Pad11)") (class "Default")
      (node (ref "U2") (pin "11") (pinfunction "RI#_11") (pintype "input+no_connect"))
    )
    (net (code "111") (name "unconnected-(U2-RTS#-Pad14)") (class "Default")
      (node (ref "U2") (pin "14") (pinfunction "RTS#_14") (pintype "input+no_connect"))
    )
    (net (code "112") (name "unconnected-(U4-BP-Pad4)") (class "Default")
      (node (ref "U4") (pin "4") (pinfunction "BP_4") (pintype "input+no_connect"))
    )
    (net (code "113") (name "unconnected-(U5-PC14-OSC32_IN-Pad2)") (class "Default")
      (node (ref "U5") (pin "2") (pinfunction "PC14-OSC32_IN_2") (pintype "input+no_connect"))
    )
  )
)
